# cryobondr-sense1-vlaqc-test1.net
KiCad netlist of a schematic drawn in EAGLE
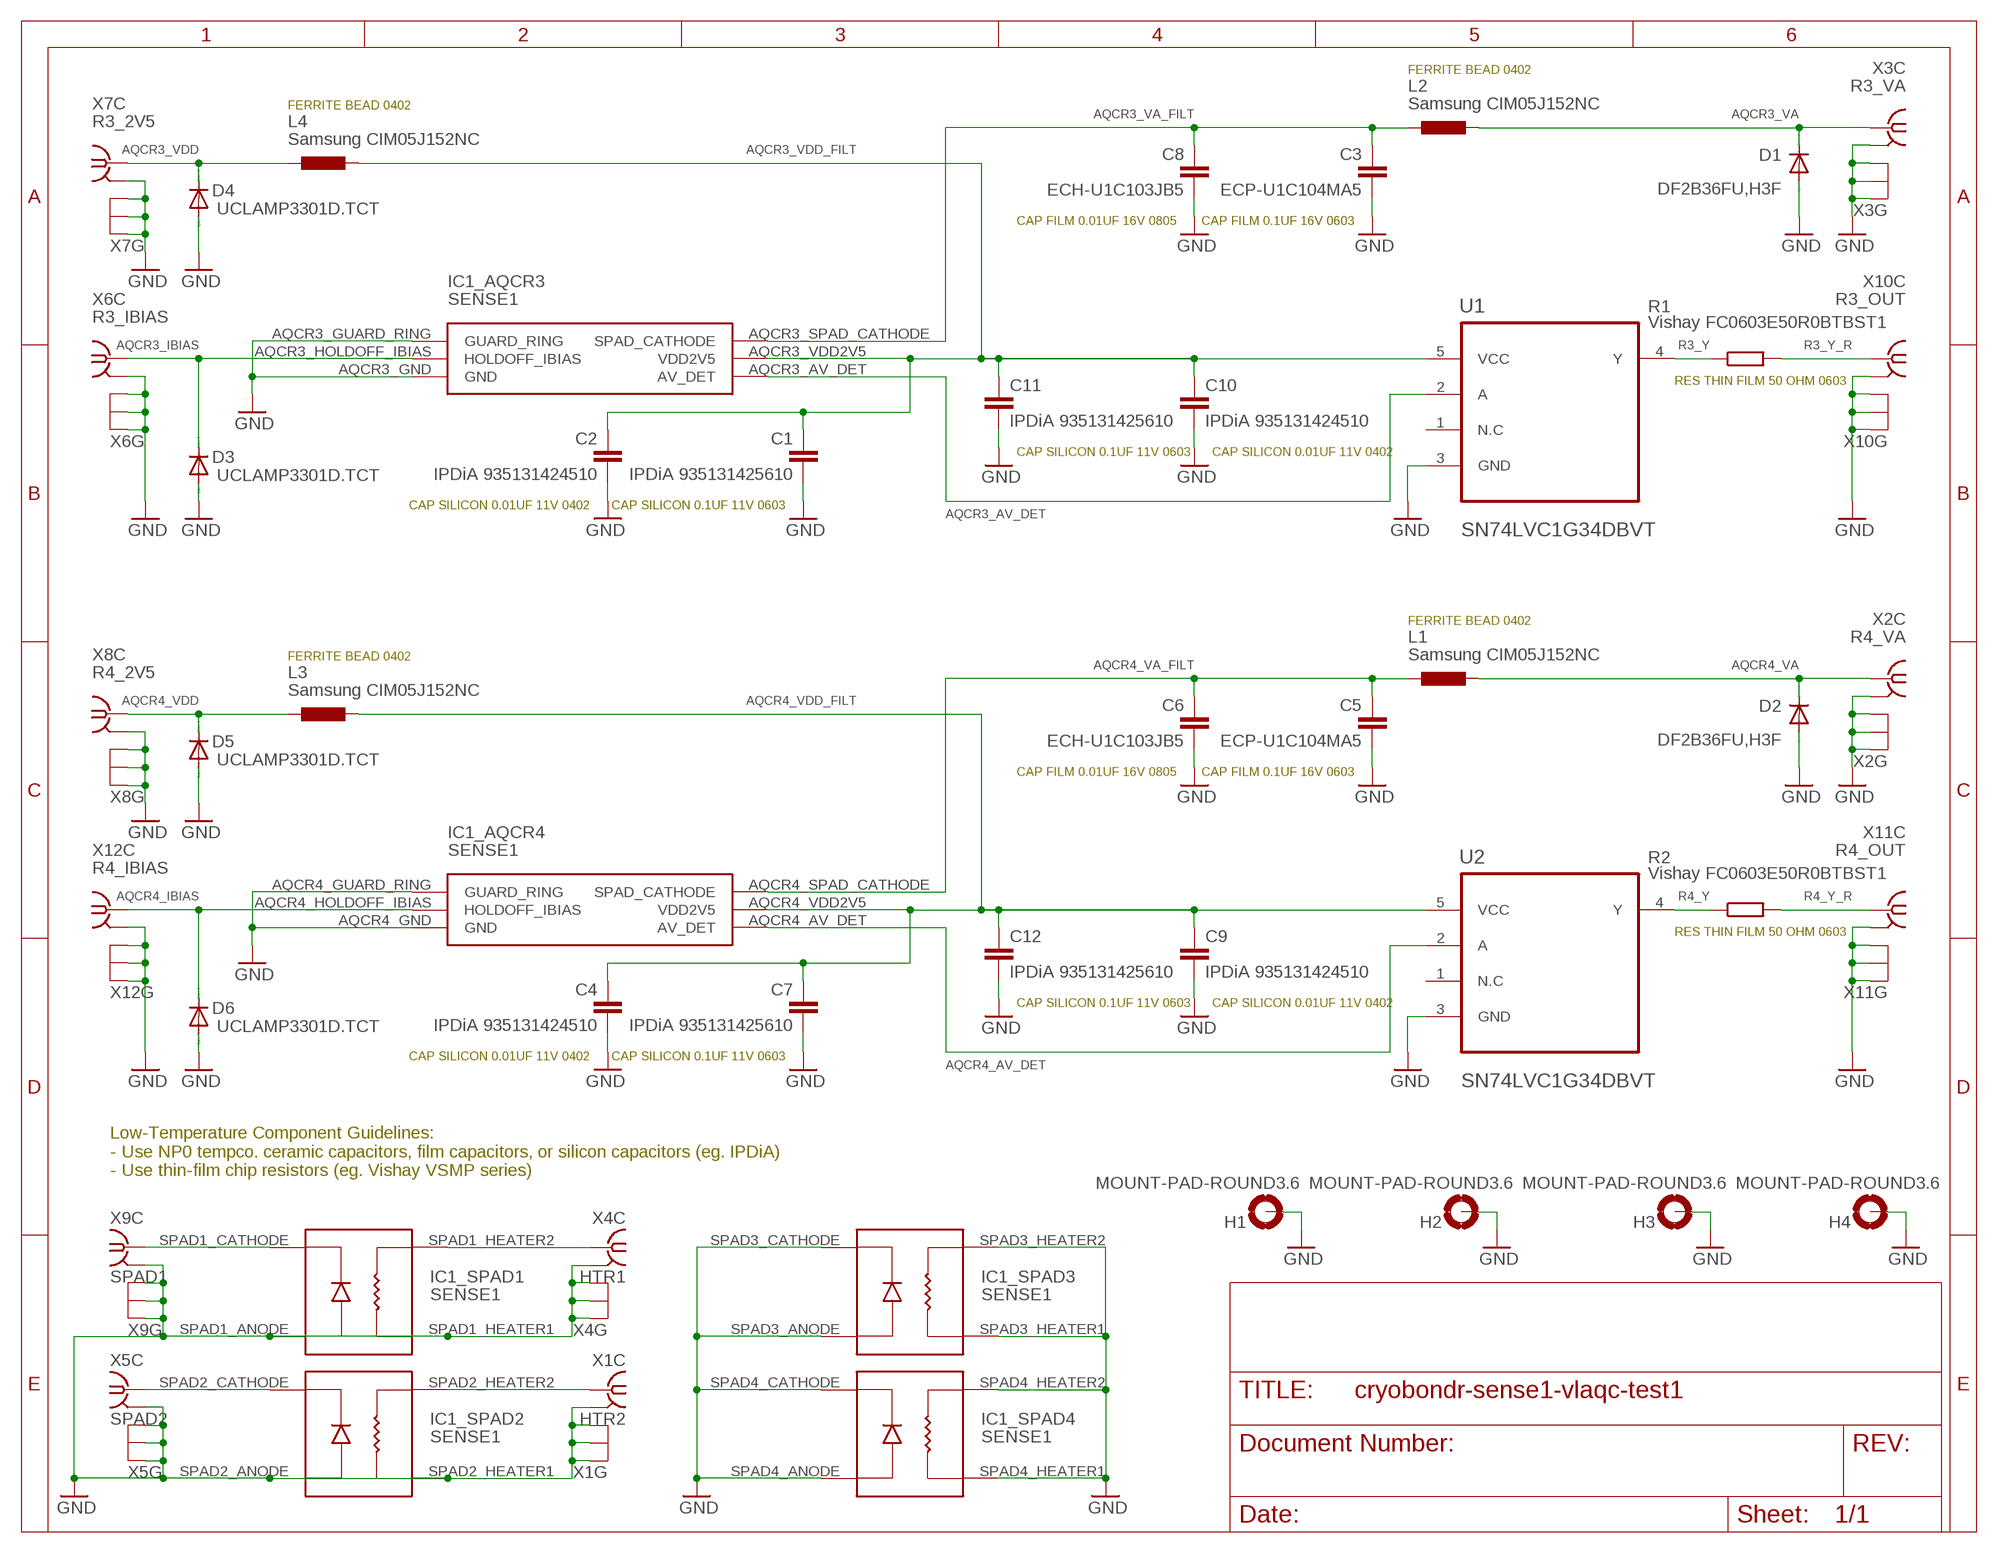
[diagram p0: schematic, sheet 1]

(export (version "E")
  (design (tool "Eeschema 10.0.6"))
  (components
    (comp (ref "C1")
      (value "IPDiA 935131425610")
      (footprint "eagle-import:C0603")
      (libsource (lib "eagle-import") (part "C-EUC0603"))
    )
    (comp (ref "C2")
      (value "IPDiA 935131424510")
      (footprint "eagle-import:C0402")
      (libsource (lib "eagle-import") (part "C-EUC0402"))
    )
    (comp (ref "C3")
      (value "ECP-U1C104MA5")
      (footprint "eagle-import:C0805")
      (libsource (lib "eagle-import") (part "C-EUC0805"))
    )
    (comp (ref "C4")
      (value "IPDiA 935131424510")
      (footprint "eagle-import:C0402")
      (libsource (lib "eagle-import") (part "C-EUC0402"))
    )
    (comp (ref "C5")
      (value "ECP-U1C104MA5")
      (footprint "eagle-import:C0805")
      (libsource (lib "eagle-import") (part "C-EUC0805"))
    )
    (comp (ref "C6")
      (value "ECH-U1C103JB5")
      (footprint "eagle-import:C0805")
      (libsource (lib "eagle-import") (part "C-EUC0805"))
    )
    (comp (ref "C7")
      (value "IPDiA 935131425610")
      (footprint "eagle-import:C0603")
      (libsource (lib "eagle-import") (part "C-EUC0603"))
    )
    (comp (ref "C8")
      (value "ECH-U1C103JB5")
      (footprint "eagle-import:C0805")
      (libsource (lib "eagle-import") (part "C-EUC0805"))
    )
    (comp (ref "C9")
      (value "IPDiA 935131424510")
      (footprint "eagle-import:C0402")
      (libsource (lib "eagle-import") (part "C-EUC0402"))
    )
    (comp (ref "C10")
      (value "IPDiA 935131424510")
      (footprint "eagle-import:C0402")
      (libsource (lib "eagle-import") (part "C-EUC0402"))
    )
    (comp (ref "C11")
      (value "IPDiA 935131425610")
      (footprint "eagle-import:C0603")
      (libsource (lib "eagle-import") (part "C-EUC0603"))
    )
    (comp (ref "C12")
      (value "IPDiA 935131425610")
      (footprint "eagle-import:C0603")
      (libsource (lib "eagle-import") (part "C-EUC0603"))
    )
    (comp (ref "D1")
      (value "DF2B36FU,H3F")
      (footprint "eagle-import:SOD323-W")
      (libsource (lib "eagle-import") (part "DIODE-SOD323-W"))
    )
    (comp (ref "D2")
      (value "DF2B36FU,H3F")
      (footprint "eagle-import:SOD323-W")
      (libsource (lib "eagle-import") (part "DIODE-SOD323-W"))
    )
    (comp (ref "D3")
      (value "UCLAMP3301D.TCT")
      (footprint "eagle-import:SOD323-W")
      (libsource (lib "eagle-import") (part "DIODE-SOD323-W"))
    )
    (comp (ref "D4")
      (value "UCLAMP3301D.TCT")
      (footprint "eagle-import:SOD323-W")
      (libsource (lib "eagle-import") (part "DIODE-SOD323-W"))
    )
    (comp (ref "D5")
      (value "UCLAMP3301D.TCT")
      (footprint "eagle-import:SOD323-W")
      (libsource (lib "eagle-import") (part "DIODE-SOD323-W"))
    )
    (comp (ref "D6")
      (value "UCLAMP3301D.TCT")
      (footprint "eagle-import:SOD323-W")
      (libsource (lib "eagle-import") (part "DIODE-SOD323-W"))
    )
    (comp (ref "H1")
      (value "MOUNT-PAD-ROUND3.6")
      (footprint "eagle-import:3,6-PAD")
      (libsource (lib "eagle-import") (part "MOUNT-PAD-ROUND3.6"))
    )
    (comp (ref "H2")
      (value "MOUNT-PAD-ROUND3.6")
      (footprint "eagle-import:3,6-PAD")
      (libsource (lib "eagle-import") (part "MOUNT-PAD-ROUND3.6"))
    )
    (comp (ref "H3")
      (value "MOUNT-PAD-ROUND3.6")
      (footprint "eagle-import:3,6-PAD")
      (libsource (lib "eagle-import") (part "MOUNT-PAD-ROUND3.6"))
    )
    (comp (ref "H4")
      (value "MOUNT-PAD-ROUND3.6")
      (footprint "eagle-import:3,6-PAD")
      (libsource (lib "eagle-import") (part "MOUNT-PAD-ROUND3.6"))
    )
    (comp (ref "IC1")
      (value "SENSE1")
      (footprint "eagle-import:SENSE1-WIREBOND-VLAQC-TEST1")
      (libsource (lib "eagle-import") (part "SENSE1-WIREBOND-VLAQC-TEST1"))
    )
    (comp (ref "L1")
      (value "Samsung CIM05J152NC")
      (footprint "eagle-import:R0402")
      (libsource (lib "eagle-import") (part "INDUCTOR0402"))
    )
    (comp (ref "L2")
      (value "Samsung CIM05J152NC")
      (footprint "eagle-import:R0402")
      (libsource (lib "eagle-import") (part "INDUCTOR0402"))
    )
    (comp (ref "L3")
      (value "Samsung CIM05J152NC")
      (footprint "eagle-import:R0402")
      (libsource (lib "eagle-import") (part "INDUCTOR0402"))
    )
    (comp (ref "L4")
      (value "Samsung CIM05J152NC")
      (footprint "eagle-import:R0402")
      (libsource (lib "eagle-import") (part "INDUCTOR0402"))
    )
    (comp (ref "R1")
      (value "Vishay FC0603E50R0BTBST1")
      (footprint "eagle-import:R0603")
      (libsource (lib "eagle-import") (part "R-EU_R0603"))
    )
    (comp (ref "R2")
      (value "Vishay FC0603E50R0BTBST1")
      (footprint "eagle-import:R0603")
      (libsource (lib "eagle-import") (part "R-EU_R0603"))
    )
    (comp (ref "U1")
      (value "SN74LVC1G34DBVT")
      (footprint "eagle-import:SOT95P280X145-5N")
      (fields (field (name "SPICEPREFIX") "X"))
      (libsource (lib "eagle-import") (part "SN74LVC1G34DBVT"))
    )
    (comp (ref "U2")
      (value "SN74LVC1G34DBVT")
      (footprint "eagle-import:SOT95P280X145-5N")
      (fields (field (name "SPICEPREFIX") "X"))
      (libsource (lib "eagle-import") (part "SN74LVC1G34DBVT"))
    )
    (comp (ref "X1")
      (value "HTR2")
      (footprint "eagle-import:MMCX-SMT-BIGPADS")
      (libsource (lib "eagle-import") (part "MMCXBIGPAD"))
    )
    (comp (ref "X2")
      (value "R4_VA")
      (footprint "eagle-import:MMCX-SMT-BIGPADS")
      (libsource (lib "eagle-import") (part "MMCXBIGPAD"))
    )
    (comp (ref "X3")
      (value "R3_VA")
      (footprint "eagle-import:MMCX-SMT-BIGPADS")
      (libsource (lib "eagle-import") (part "MMCXBIGPAD"))
    )
    (comp (ref "X4")
      (value "HTR1")
      (footprint "eagle-import:MMCX-SMT-BIGPADS")
      (libsource (lib "eagle-import") (part "MMCXBIGPAD"))
    )
    (comp (ref "X5")
      (value "SPAD2")
      (footprint "eagle-import:MMCX-SMT-BIGPADS")
      (libsource (lib "eagle-import") (part "MMCXBIGPAD"))
    )
    (comp (ref "X6")
      (value "R3_IBIAS")
      (footprint "eagle-import:MMCX-SMT-BIGPADS")
      (libsource (lib "eagle-import") (part "MMCXBIGPAD"))
    )
    (comp (ref "X7")
      (value "R3_2V5")
      (footprint "eagle-import:MMCX-SMT-BIGPADS")
      (libsource (lib "eagle-import") (part "MMCXBIGPAD"))
    )
    (comp (ref "X8")
      (value "R4_2V5")
      (footprint "eagle-import:MMCX-SMT-BIGPADS")
      (libsource (lib "eagle-import") (part "MMCXBIGPAD"))
    )
    (comp (ref "X9")
      (value "SPAD1")
      (footprint "eagle-import:MMCX-SMT-BIGPADS")
      (libsource (lib "eagle-import") (part "MMCXBIGPAD"))
    )
    (comp (ref "X10")
      (value "R3_OUT")
      (footprint "eagle-import:MMCX-SMT-BIGPADS")
      (libsource (lib "eagle-import") (part "MMCXBIGPAD"))
    )
    (comp (ref "X11")
      (value "R4_OUT")
      (footprint "eagle-import:MMCX-SMT-BIGPADS")
      (libsource (lib "eagle-import") (part "MMCXBIGPAD"))
    )
    (comp (ref "X12")
      (value "R4_IBIAS")
      (footprint "eagle-import:MMCX-SMT-BIGPADS")
      (libsource (lib "eagle-import") (part "MMCXBIGPAD"))
    )
  )
  (nets
    (net (code "1") (name "/AQCR3_AV_DET") (class "Default")
      (node (ref "IC1") (pin "AQCR3_AV_DET") (pinfunction "AV_DET_AQCR3_AV_DET") (pintype "bidirectional"))
      (node (ref "U1") (pin "2") (pinfunction "A_2") (pintype "input"))
    )
    (net (code "2") (name "/AQCR3_IBIAS") (class "Default")
      (node (ref "D3") (pin "C") (pinfunction "C_C") (pintype "passive"))
      (node (ref "IC1") (pin "AQCR3_HOLDOFF_IBIAS") (pinfunction "HOLDOFF_IBIAS_AQCR3_HOLDOFF_IBIAS") (pintype "bidirectional"))
      (node (ref "X6") (pin "S") (pinfunction "1_S") (pintype "passive"))
    )
    (net (code "3") (name "/AQCR3_VA") (class "Default")
      (node (ref "D1") (pin "C") (pinfunction "C_C") (pintype "passive"))
      (node (ref "L2") (pin "2") (pinfunction "P$2_2") (pintype "bidirectional"))
      (node (ref "X3") (pin "S") (pinfunction "1_S") (pintype "passive"))
    )
    (net (code "4") (name "/AQCR3_VA_FILT") (class "Default")
      (node (ref "C3") (pin "1") (pinfunction "1_1") (pintype "passive"))
      (node (ref "C8") (pin "1") (pinfunction "1_1") (pintype "passive"))
      (node (ref "IC1") (pin "AQCR3_SPAD_CATHODE") (pinfunction "SPAD_CATHODE_AQCR3_SPAD_CATHODE") (pintype "bidirectional"))
      (node (ref "L2") (pin "1") (pinfunction "P$1_1") (pintype "bidirectional"))
    )
    (net (code "5") (name "/AQCR3_VDD") (class "Default")
      (node (ref "D4") (pin "C") (pinfunction "C_C") (pintype "passive"))
      (node (ref "L4") (pin "1") (pinfunction "P$1_1") (pintype "bidirectional"))
      (node (ref "X7") (pin "S") (pinfunction "1_S") (pintype "passive"))
    )
    (net (code "6") (name "/AQCR3_VDD_FILT") (class "Default")
      (node (ref "C1") (pin "1") (pinfunction "1_1") (pintype "passive"))
      (node (ref "C10") (pin "1") (pinfunction "1_1") (pintype "passive"))
      (node (ref "C11") (pin "1") (pinfunction "1_1") (pintype "passive"))
      (node (ref "C2") (pin "1") (pinfunction "1_1") (pintype "passive"))
      (node (ref "IC1") (pin "AQCR3_VDD2V5") (pinfunction "VDD2V5_AQCR3_VDD2V5") (pintype "bidirectional"))
      (node (ref "L4") (pin "2") (pinfunction "P$2_2") (pintype "bidirectional"))
      (node (ref "U1") (pin "5") (pinfunction "VCC_5") (pintype "power_in"))
    )
    (net (code "7") (name "/AQCR4_AV_DET") (class "Default")
      (node (ref "IC1") (pin "AQCR4_AV_DET") (pinfunction "AV_DET_AQCR4_AV_DET") (pintype "bidirectional"))
      (node (ref "U2") (pin "2") (pinfunction "A_2") (pintype "input"))
    )
    (net (code "8") (name "/AQCR4_IBIAS") (class "Default")
      (node (ref "D6") (pin "C") (pinfunction "C_C") (pintype "passive"))
      (node (ref "IC1") (pin "AQCR4_HOLDOFF_IBIAS") (pinfunction "HOLDOFF_IBIAS_AQCR4_HOLDOFF_IBIAS") (pintype "bidirectional"))
      (node (ref "X12") (pin "S") (pinfunction "1_S") (pintype "passive"))
    )
    (net (code "9") (name "/AQCR4_VA") (class "Default")
      (node (ref "D2") (pin "C") (pinfunction "C_C") (pintype "passive"))
      (node (ref "L1") (pin "2") (pinfunction "P$2_2") (pintype "bidirectional"))
      (node (ref "X2") (pin "S") (pinfunction "1_S") (pintype "passive"))
    )
    (net (code "10") (name "/AQCR4_VA_FILT") (class "Default")
      (node (ref "C5") (pin "1") (pinfunction "1_1") (pintype "passive"))
      (node (ref "C6") (pin "1") (pinfunction "1_1") (pintype "passive"))
      (node (ref "IC1") (pin "AQCR4_SPAD_CATHODE") (pinfunction "SPAD_CATHODE_AQCR4_SPAD_CATHODE") (pintype "bidirectional"))
      (node (ref "L1") (pin "1") (pinfunction "P$1_1") (pintype "bidirectional"))
    )
    (net (code "11") (name "/AQCR4_VDD") (class "Default")
      (node (ref "D5") (pin "C") (pinfunction "C_C") (pintype "passive"))
      (node (ref "L3") (pin "1") (pinfunction "P$1_1") (pintype "bidirectional"))
      (node (ref "X8") (pin "S") (pinfunction "1_S") (pintype "passive"))
    )
    (net (code "12") (name "/AQCR4_VDD_FILT") (class "Default")
      (node (ref "C12") (pin "1") (pinfunction "1_1") (pintype "passive"))
      (node (ref "C4") (pin "1") (pinfunction "1_1") (pintype "passive"))
      (node (ref "C7") (pin "1") (pinfunction "1_1") (pintype "passive"))
      (node (ref "C9") (pin "1") (pinfunction "1_1") (pintype "passive"))
      (node (ref "IC1") (pin "AQCR4_VDD2V5") (pinfunction "VDD2V5_AQCR4_VDD2V5") (pintype "bidirectional"))
      (node (ref "L3") (pin "2") (pinfunction "P$2_2") (pintype "bidirectional"))
      (node (ref "U2") (pin "5") (pinfunction "VCC_5") (pintype "power_in"))
    )
    (net (code "13") (name "/R3_Y") (class "Default")
      (node (ref "R1") (pin "1") (pinfunction "1_1") (pintype "passive"))
      (node (ref "U1") (pin "4") (pinfunction "Y_4") (pintype "output"))
    )
    (net (code "14") (name "/R3_Y_R") (class "Default")
      (node (ref "R1") (pin "2") (pinfunction "2_2") (pintype "passive"))
      (node (ref "X10") (pin "S") (pinfunction "1_S") (pintype "passive"))
    )
    (net (code "15") (name "/R4_Y") (class "Default")
      (node (ref "R2") (pin "1") (pinfunction "1_1") (pintype "passive"))
      (node (ref "U2") (pin "4") (pinfunction "Y_4") (pintype "output"))
    )
    (net (code "16") (name "/R4_Y_R") (class "Default")
      (node (ref "R2") (pin "2") (pinfunction "2_2") (pintype "passive"))
      (node (ref "X11") (pin "S") (pinfunction "1_S") (pintype "passive"))
    )
    (net (code "17") (name "GND") (class "Default")
      (node (ref "C1") (pin "2") (pinfunction "2_2") (pintype "passive"))
      (node (ref "C10") (pin "2") (pinfunction "2_2") (pintype "passive"))
      (node (ref "C11") (pin "2") (pinfunction "2_2") (pintype "passive"))
      (node (ref "C12") (pin "2") (pinfunction "2_2") (pintype "passive"))
      (node (ref "C2") (pin "2") (pinfunction "2_2") (pintype "passive"))
      (node (ref "C3") (pin "2") (pinfunction "2_2") (pintype "passive"))
      (node (ref "C4") (pin "2") (pinfunction "2_2") (pintype "passive"))
      (node (ref "C5") (pin "2") (pinfunction "2_2") (pintype "passive"))
      (node (ref "C6") (pin "2") (pinfunction "2_2") (pintype "passive"))
      (node (ref "C7") (pin "2") (pinfunction "2_2") (pintype "passive"))
      (node (ref "C8") (pin "2") (pinfunction "2_2") (pintype "passive"))
      (node (ref "C9") (pin "2") (pinfunction "2_2") (pintype "passive"))
      (node (ref "D1") (pin "A") (pinfunction "A_A") (pintype "passive"))
      (node (ref "D2") (pin "A") (pinfunction "A_A") (pintype "passive"))
      (node (ref "D3") (pin "A") (pinfunction "A_A") (pintype "passive"))
      (node (ref "D4") (pin "A") (pinfunction "A_A") (pintype "passive"))
      (node (ref "D5") (pin "A") (pinfunction "A_A") (pintype "passive"))
      (node (ref "D6") (pin "A") (pinfunction "A_A") (pintype "passive"))
      (node (ref "H1") (pin "B3,6") (pinfunction "MOUNT_B3,6") (pintype "passive"))
      (node (ref "H2") (pin "B3,6") (pinfunction "MOUNT_B3,6") (pintype "passive"))
      (node (ref "H3") (pin "B3,6") (pinfunction "MOUNT_B3,6") (pintype "passive"))
      (node (ref "H4") (pin "B3,6") (pinfunction "MOUNT_B3,6") (pintype "passive"))
      (node (ref "IC1") (pin "AQCR3_GND") (pinfunction "GND_AQCR3_GND") (pintype "bidirectional"))
      (node (ref "IC1") (pin "AQCR3_GUARD_RING") (pinfunction "GUARD_RING_AQCR3_GUARD_RING") (pintype "bidirectional"))
      (node (ref "IC1") (pin "AQCR4_GND") (pinfunction "GND_AQCR4_GND") (pintype "bidirectional"))
      (node (ref "IC1") (pin "AQCR4_GUARD_RING") (pinfunction "GUARD_RING_AQCR4_GUARD_RING") (pintype "bidirectional"))
      (node (ref "IC1") (pin "SPAD1_ANODE") (pinfunction "SPAD_ANODE_SPAD1_ANODE") (pintype "bidirectional"))
      (node (ref "IC1") (pin "SPAD1_HEATER1") (pinfunction "SPAD_HEATER1_SPAD1_HEATER1") (pintype "bidirectional"))
      (node (ref "IC1") (pin "SPAD2_ANODE") (pinfunction "SPAD_ANODE_SPAD2_ANODE") (pintype "bidirectional"))
      (node (ref "IC1") (pin "SPAD2_HEATER1") (pinfunction "SPAD_HEATER1_SPAD2_HEATER1") (pintype "bidirectional"))
      (node (ref "IC1") (pin "SPAD3_ANODE") (pinfunction "SPAD_ANODE_SPAD3_ANODE") (pintype "bidirectional"))
      (node (ref "IC1") (pin "SPAD3_CATHODE") (pinfunction "SPAD_CATHODE_SPAD3_CATHODE") (pintype "bidirectional"))
      (node (ref "IC1") (pin "SPAD3_HEATER1") (pinfunction "SPAD_HEATER1_SPAD3_HEATER1") (pintype "bidirectional"))
      (node (ref "IC1") (pin "SPAD3_HEATER2") (pinfunction "SPAD_HEATER2_SPAD3_HEATER2") (pintype "bidirectional"))
      (node (ref "IC1") (pin "SPAD4_ANODE") (pinfunction "SPAD_ANODE_SPAD4_ANODE") (pintype "bidirectional"))
      (node (ref "IC1") (pin "SPAD4_CATHODE") (pinfunction "SPAD_CATHODE_SPAD4_CATHODE") (pintype "bidirectional"))
      (node (ref "IC1") (pin "SPAD4_HEATER1") (pinfunction "SPAD_HEATER1_SPAD4_HEATER1") (pintype "bidirectional"))
      (node (ref "IC1") (pin "SPAD4_HEATER2") (pinfunction "SPAD_HEATER2_SPAD4_HEATER2") (pintype "bidirectional"))
      (node (ref "U1") (pin "3") (pinfunction "GND_3") (pintype "passive"))
      (node (ref "U2") (pin "3") (pinfunction "GND_3") (pintype "passive"))
      (node (ref "X1") (pin "G1") (pinfunction "GND_G1") (pintype "power_in"))
      (node (ref "X1") (pin "G2") (pinfunction "GND_G2") (pintype "power_in"))
      (node (ref "X1") (pin "G3") (pinfunction "GND_G3") (pintype "power_in"))
      (node (ref "X1") (pin "G4") (pinfunction "GND_G4") (pintype "power_in"))
      (node (ref "X10") (pin "G1") (pinfunction "GND_G1") (pintype "power_in"))
      (node (ref "X10") (pin "G2") (pinfunction "GND_G2") (pintype "power_in"))
      (node (ref "X10") (pin "G3") (pinfunction "GND_G3") (pintype "power_in"))
      (node (ref "X10") (pin "G4") (pinfunction "GND_G4") (pintype "power_in"))
      (node (ref "X11") (pin "G1") (pinfunction "GND_G1") (pintype "power_in"))
      (node (ref "X11") (pin "G2") (pinfunction "GND_G2") (pintype "power_in"))
      (node (ref "X11") (pin "G3") (pinfunction "GND_G3") (pintype "power_in"))
      (node (ref "X11") (pin "G4") (pinfunction "GND_G4") (pintype "power_in"))
      (node (ref "X12") (pin "G1") (pinfunction "GND_G1") (pintype "power_in"))
      (node (ref "X12") (pin "G2") (pinfunction "GND_G2") (pintype "power_in"))
      (node (ref "X12") (pin "G3") (pinfunction "GND_G3") (pintype "power_in"))
      (node (ref "X12") (pin "G4") (pinfunction "GND_G4") (pintype "power_in"))
      (node (ref "X2") (pin "G1") (pinfunction "GND_G1") (pintype "power_in"))
      (node (ref "X2") (pin "G2") (pinfunction "GND_G2") (pintype "power_in"))
      (node (ref "X2") (pin "G3") (pinfunction "GND_G3") (pintype "power_in"))
      (node (ref "X2") (pin "G4") (pinfunction "GND_G4") (pintype "power_in"))
      (node (ref "X3") (pin "G1") (pinfunction "GND_G1") (pintype "power_in"))
      (node (ref "X3") (pin "G2") (pinfunction "GND_G2") (pintype "power_in"))
      (node (ref "X3") (pin "G3") (pinfunction "GND_G3") (pintype "power_in"))
      (node (ref "X3") (pin "G4") (pinfunction "GND_G4") (pintype "power_in"))
      (node (ref "X4") (pin "G1") (pinfunction "GND_G1") (pintype "power_in"))
      (node (ref "X4") (pin "G2") (pinfunction "GND_G2") (pintype "power_in"))
      (node (ref "X4") (pin "G3") (pinfunction "GND_G3") (pintype "power_in"))
      (node (ref "X4") (pin "G4") (pinfunction "GND_G4") (pintype "power_in"))
      (node (ref "X5") (pin "G1") (pinfunction "GND_G1") (pintype "power_in"))
      (node (ref "X5") (pin "G2") (pinfunction "GND_G2") (pintype "power_in"))
      (node (ref "X5") (pin "G3") (pinfunction "GND_G3") (pintype "power_in"))
      (node (ref "X5") (pin "G4") (pinfunction "GND_G4") (pintype "power_in"))
      (node (ref "X6") (pin "G1") (pinfunction "GND_G1") (pintype "power_in"))
      (node (ref "X6") (pin "G2") (pinfunction "GND_G2") (pintype "power_in"))
      (node (ref "X6") (pin "G3") (pinfunction "GND_G3") (pintype "power_in"))
      (node (ref "X6") (pin "G4") (pinfunction "GND_G4") (pintype "power_in"))
      (node (ref "X7") (pin "G1") (pinfunction "GND_G1") (pintype "power_in"))
      (node (ref "X7") (pin "G2") (pinfunction "GND_G2") (pintype "power_in"))
      (node (ref "X7") (pin "G3") (pinfunction "GND_G3") (pintype "power_in"))
      (node (ref "X7") (pin "G4") (pinfunction "GND_G4") (pintype "power_in"))
      (node (ref "X8") (pin "G1") (pinfunction "GND_G1") (pintype "power_in"))
      (node (ref "X8") (pin "G2") (pinfunction "GND_G2") (pintype "power_in"))
      (node (ref "X8") (pin "G3") (pinfunction "GND_G3") (pintype "power_in"))
      (node (ref "X8") (pin "G4") (pinfunction "GND_G4") (pintype "power_in"))
      (node (ref "X9") (pin "G1") (pinfunction "GND_G1") (pintype "power_in"))
      (node (ref "X9") (pin "G2") (pinfunction "GND_G2") (pintype "power_in"))
      (node (ref "X9") (pin "G3") (pinfunction "GND_G3") (pintype "power_in"))
      (node (ref "X9") (pin "G4") (pinfunction "GND_G4") (pintype "power_in"))
    )
    (net (code "18") (name "Net-(IC1C-SPAD_CATHODE)") (class "Default")
      (node (ref "IC1") (pin "SPAD1_CATHODE") (pinfunction "SPAD_CATHODE_SPAD1_CATHODE") (pintype "bidirectional"))
      (node (ref "X9") (pin "S") (pinfunction "1_S") (pintype "passive"))
    )
    (net (code "19") (name "Net-(IC1C-SPAD_HEATER2)") (class "Default")
      (node (ref "IC1") (pin "SPAD1_HEATER2") (pinfunction "SPAD_HEATER2_SPAD1_HEATER2") (pintype "bidirectional"))
      (node (ref "X4") (pin "S") (pinfunction "1_S") (pintype "passive"))
    )
    (net (code "20") (name "Net-(IC1D-SPAD_CATHODE)") (class "Default")
      (node (ref "IC1") (pin "SPAD2_CATHODE") (pinfunction "SPAD_CATHODE_SPAD2_CATHODE") (pintype "bidirectional"))
      (node (ref "X5") (pin "S") (pinfunction "1_S") (pintype "passive"))
    )
    (net (code "21") (name "Net-(IC1D-SPAD_HEATER2)") (class "Default")
      (node (ref "IC1") (pin "SPAD2_HEATER2") (pinfunction "SPAD_HEATER2_SPAD2_HEATER2") (pintype "bidirectional"))
      (node (ref "X1") (pin "S") (pinfunction "1_S") (pintype "passive"))
    )
    (net (code "22") (name "unconnected-(U1-N.C-Pad1)") (class "Default")
      (node (ref "U1") (pin "1") (pinfunction "N.C_1") (pintype "no_connect"))
    )
    (net (code "23") (name "unconnected-(U2-N.C-Pad1)") (class "Default")
      (node (ref "U2") (pin "1") (pinfunction "N.C_1") (pintype "no_connect"))
    )
  )
)
